# Preamp.net
KiCad netlist of a schematic drawn in EAGLE
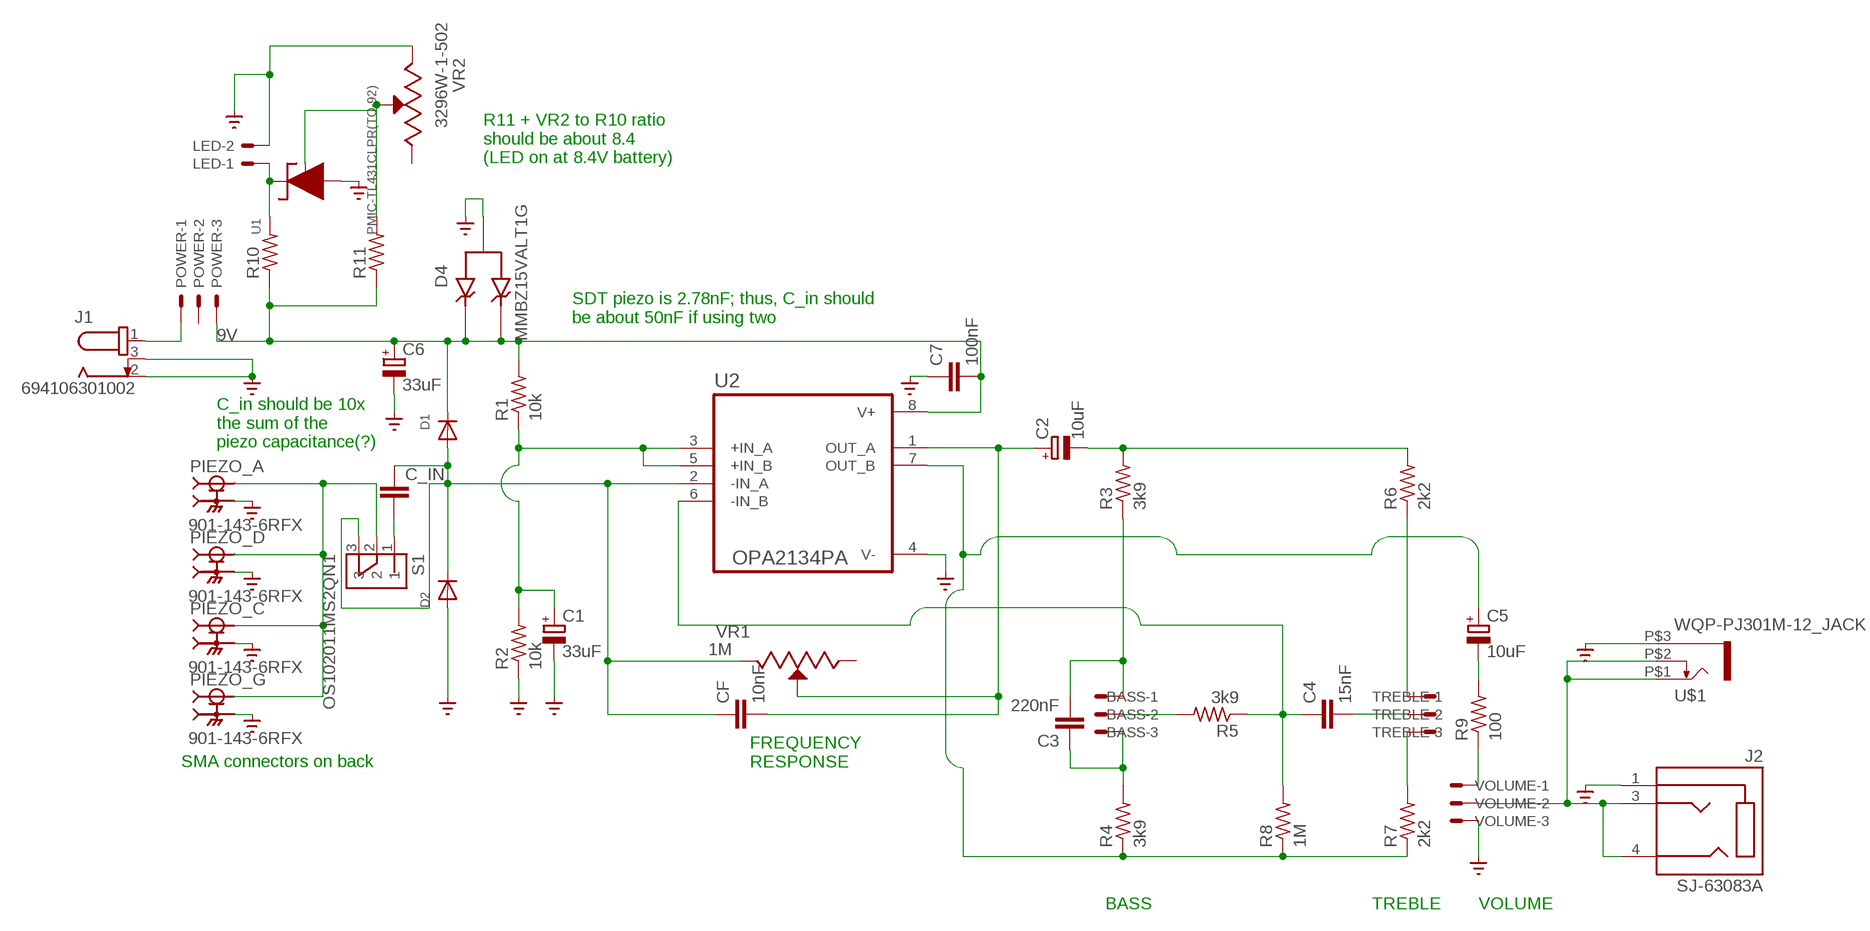
[diagram p0: schematic, sheet 1]

(export (version "E")
  (design (tool "Eeschema 10.0.6"))
  (components
    (comp (ref "BASS")
      (value "JST-XH-03-PIN-LONG-PAD")
      (footprint "eagle-import:JST-XH-03-PACKAGE-LONG-PAD")
      (libsource (lib "eagle-import") (part "JST-XH-03-PIN-LONG-PAD"))
    )
    (comp (ref "C1")
      (value "33uF")
      (footprint "eagle-import:E2,5-6")
      (libsource (lib "eagle-import") (part "CPOL-EUE2.5-6"))
    )
    (comp (ref "C2")
      (value "10uF")
      (footprint "eagle-import:E2,5-6")
      (libsource (lib "eagle-import") (part "CPOL-EUE2.5-6"))
    )
    (comp (ref "C3")
      (value "220nF")
      (footprint "eagle-import:C1206")
      (libsource (lib "eagle-import") (part "C-EUC1206"))
    )
    (comp (ref "C4")
      (value "15nF")
      (footprint "eagle-import:C1206")
      (libsource (lib "eagle-import") (part "C-EUC1206"))
    )
    (comp (ref "C5")
      (value "10uF")
      (footprint "eagle-import:E2,5-6")
      (libsource (lib "eagle-import") (part "CPOL-EUE2.5-6"))
    )
    (comp (ref "C6")
      (value "33uF")
      (footprint "eagle-import:E2,5-6")
      (libsource (lib "eagle-import") (part "CPOL-EUE2.5-6"))
    )
    (comp (ref "C7")
      (value "100nF")
      (footprint "eagle-import:C0603")
      (libsource (lib "eagle-import") (part "C-EUC0603"))
    )
    (comp (ref "CF")
      (value "10nF")
      (footprint "eagle-import:C1206")
      (libsource (lib "eagle-import") (part "C-EUC1206"))
    )
    (comp (ref "C_IN")
      (value "C-EUC0603")
      (footprint "eagle-import:C0603")
      (libsource (lib "eagle-import") (part "C-EUC0603"))
    )
    (comp (ref "D1")
      (value "DIODEDO-1N4148")
      (footprint "eagle-import:DO-1N4148")
      (libsource (lib "eagle-import") (part "DIODEDO-1N4148"))
    )
    (comp (ref "D2")
      (value "DIODEDO-1N4148")
      (footprint "eagle-import:DO-1N4148")
      (libsource (lib "eagle-import") (part "DIODEDO-1N4148"))
    )
    (comp (ref "D4")
      (value "MMBZ15VALT1G")
      (footprint "eagle-import:SOT95P237X111-3N")
      (fields
        (field (name "DIGI-KEY_PART_NUMBER") "MMBZ15VALT1GOSCT-ND")
        (field (name "MF") "ON Semiconductor")
      )
      (libsource (lib "eagle-import") (part "MMBZ15VALT1G"))
    )
    (comp (ref "J1")
      (value "694106301002")
      (footprint "eagle-import:694106301002")
      (fields
        (field (name "DIGIKEY_PART_NUMBER") "732-5930-ND")
        (field (name "MANUFACTURER") "Wurth Electronics Inc.")
        (field (name "CREATED_BY") "PCBLayout.com")
      )
      (libsource (lib "eagle-import") (part "694106301002"))
    )
    (comp (ref "J2")
      (value "SJ-63083A")
      (footprint "eagle-import:CUI_SJ-63083A")
      (fields (field (name "DIGI-KEY_PART_NUMBER") "2223-SJ-63083A-ND") (field (name "MF") "CUI Devices"))
      (libsource (lib "eagle-import") (part "SJ-63083A"))
    )
    (comp (ref "LED")
      (value "JST-XH-02-PIN-ROUND-PAD")
      (footprint "eagle-import:JST-XH-02-PACKAGE-ROUND-PAD")
      (libsource (lib "eagle-import") (part "JST-XH-02-PIN-ROUND-PAD"))
    )
    (comp (ref "PIEZO_A")
      (value "901-143-6RFX")
      (footprint "eagle-import:AMPHENOL_901-143-6RFX")
      (fields (field (name "MF") "Amphenol RF"))
      (libsource (lib "eagle-import") (part "901-143-6RFX"))
    )
    (comp (ref "PIEZO_C")
      (value "901-143-6RFX")
      (footprint "eagle-import:AMPHENOL_901-143-6RFX")
      (fields (field (name "MF") "Amphenol RF"))
      (libsource (lib "eagle-import") (part "901-143-6RFX"))
    )
    (comp (ref "PIEZO_D")
      (value "901-143-6RFX")
      (footprint "eagle-import:AMPHENOL_901-143-6RFX")
      (fields (field (name "MF") "Amphenol RF"))
      (libsource (lib "eagle-import") (part "901-143-6RFX"))
    )
    (comp (ref "PIEZO_G")
      (value "901-143-6RFX")
      (footprint "eagle-import:AMPHENOL_901-143-6RFX")
      (fields (field (name "MF") "Amphenol RF"))
      (libsource (lib "eagle-import") (part "901-143-6RFX"))
    )
    (comp (ref "POWER")
      (value "JST-XH-03-PIN-LONG-PAD")
      (footprint "eagle-import:JST-XH-03-PACKAGE-LONG-PAD")
      (libsource (lib "eagle-import") (part "JST-XH-03-PIN-LONG-PAD"))
    )
    (comp (ref "R1")
      (value "10k")
      (footprint "eagle-import:R1206")
      (libsource (lib "eagle-import") (part "R-US_R1206"))
    )
    (comp (ref "R2")
      (value "10k")
      (footprint "eagle-import:R1206")
      (libsource (lib "eagle-import") (part "R-US_R1206"))
    )
    (comp (ref "R3")
      (value "3k9")
      (footprint "eagle-import:R1206")
      (libsource (lib "eagle-import") (part "R-US_R1206"))
    )
    (comp (ref "R4")
      (value "3k9")
      (footprint "eagle-import:R1206")
      (libsource (lib "eagle-import") (part "R-US_R1206"))
    )
    (comp (ref "R5")
      (value "3k9")
      (footprint "eagle-import:R1206")
      (libsource (lib "eagle-import") (part "R-US_R1206"))
    )
    (comp (ref "R6")
      (value "2k2")
      (footprint "eagle-import:R1206")
      (libsource (lib "eagle-import") (part "R-US_R1206"))
    )
    (comp (ref "R7")
      (value "2k2")
      (footprint "eagle-import:R1206")
      (libsource (lib "eagle-import") (part "R-US_R1206"))
    )
    (comp (ref "R8")
      (value "1M")
      (footprint "eagle-import:R1206")
      (libsource (lib "eagle-import") (part "R-US_R1206"))
    )
    (comp (ref "R9")
      (value "100")
      (footprint "eagle-import:R1206")
      (libsource (lib "eagle-import") (part "R-US_R1206"))
    )
    (comp (ref "R10")
      (value "R-US_R1206")
      (footprint "eagle-import:R1206")
      (libsource (lib "eagle-import") (part "R-US_R1206"))
    )
    (comp (ref "R11")
      (value "R-US_R1206")
      (footprint "eagle-import:R1206")
      (libsource (lib "eagle-import") (part "R-US_R1206"))
    )
    (comp (ref "S1")
      (value "OS102011MS2QN1")
      (footprint "eagle-import:SW_OS102011MS2QN1")
      (fields (field (name "DIGI-KEY_PART_NUMBER") "CKN12284-ND") (field (name "MF") "C&K"))
      (libsource (lib "eagle-import") (part "OS102011MS2QN1"))
    )
    (comp (ref "TREBLE")
      (value "JST-XH-03-PIN-LONG-PAD")
      (footprint "eagle-import:JST-XH-03-PACKAGE-LONG-PAD")
      (libsource (lib "eagle-import") (part "JST-XH-03-PIN-LONG-PAD"))
    )
    (comp (ref "U$1")
      (value "WQP-PJ301M-12_JACK")
      (footprint "eagle-import:WQP-PJ301M-12_JACK")
      (libsource (lib "eagle-import") (part "WQP-PJ301M-12_JACK"))
    )
    (comp (ref "U1")
      (value "PMIC-TL431CLPR(TO-92)")
      (footprint "eagle-import:TO-92")
      (fields (field (name "MF") "Texas Instruments") (field (name "MP") "TL431CLPR"))
      (libsource (lib "eagle-import") (part "PMIC-TL431CLPR(TO-92)"))
    )
    (comp (ref "U2")
      (value "OPA2134PA")
      (footprint "eagle-import:DIP794W45P254L959H508Q8")
      (fields (field (name "MF") "Texas"))
      (libsource (lib "eagle-import") (part "OPA2134PA"))
    )
    (comp (ref "VOLUME")
      (value "JST-XH-03-PIN-LONG-PAD")
      (footprint "eagle-import:JST-XH-03-PACKAGE-LONG-PAD")
      (libsource (lib "eagle-import") (part "JST-XH-03-PIN-LONG-PAD"))
    )
    (comp (ref "VR1")
      (value "1M")
      (footprint "eagle-import:TRIM_3296W-1-502")
      (fields
        (field (name "DIGI-KEY_PART_NUMBER") "3296W-1-502RLFTR-ND")
        (field (name "MF") "Bourns")
        (field (name "MP") "3296W-1-502")
      )
      (libsource (lib "eagle-import") (part "3296W-1-502"))
    )
    (comp (ref "VR2")
      (value "3296W-1-502")
      (footprint "eagle-import:TRIM_3296W-1-502")
      (fields (field (name "DIGI-KEY_PART_NUMBER") "3296W-1-502RLFTR-ND") (field (name "MF") "Bourns"))
      (libsource (lib "eagle-import") (part "3296W-1-502"))
    )
  )
  (nets
    (net (code "1") (name "/9V") (class "Default")
      (node (ref "C6") (pin "+") (pinfunction "+_+") (pintype "passive"))
      (node (ref "C7") (pin "2") (pinfunction "2_2") (pintype "passive"))
      (node (ref "D1") (pin "C") (pinfunction "C_C") (pintype "passive"))
      (node (ref "D4") (pin "1") (pinfunction "K1_1") (pintype "passive"))
      (node (ref "D4") (pin "2") (pinfunction "K2_2") (pintype "passive"))
      (node (ref "POWER") (pin "3") (pinfunction "S_3") (pintype "passive"))
      (node (ref "R1") (pin "2") (pinfunction "2_2") (pintype "passive"))
      (node (ref "R10") (pin "1") (pinfunction "1_1") (pintype "passive"))
      (node (ref "R11") (pin "1") (pinfunction "1_1") (pintype "passive"))
      (node (ref "U2") (pin "8") (pinfunction "V+_8") (pintype "power_in"))
    )
    (net (code "2") (name "Net-(BASSA-S)") (class "Default")
      (node (ref "BASS") (pin "1") (pinfunction "S_1") (pintype "passive"))
      (node (ref "C3") (pin "2") (pinfunction "2_2") (pintype "passive"))
      (node (ref "R3") (pin "1") (pinfunction "1_1") (pintype "passive"))
    )
    (net (code "3") (name "Net-(BASSB-S)") (class "Default")
      (node (ref "BASS") (pin "2") (pinfunction "S_2") (pintype "passive"))
      (node (ref "R5") (pin "2") (pinfunction "2_2") (pintype "passive"))
    )
    (net (code "4") (name "Net-(BASSC-S)") (class "Default")
      (node (ref "BASS") (pin "3") (pinfunction "S_3") (pintype "passive"))
      (node (ref "C3") (pin "1") (pinfunction "1_1") (pintype "passive"))
      (node (ref "R4") (pin "2") (pinfunction "2_2") (pintype "passive"))
    )
    (net (code "5") (name "Net-(C2-Pad-)") (class "Default")
      (node (ref "C2") (pin "-") (pinfunction "-_-") (pintype "passive"))
      (node (ref "R3") (pin "2") (pinfunction "2_2") (pintype "passive"))
      (node (ref "R6") (pin "2") (pinfunction "2_2") (pintype "passive"))
    )
    (net (code "6") (name "Net-(C5-Pad-)") (class "Default")
      (node (ref "C5") (pin "-") (pinfunction "-_-") (pintype "passive"))
      (node (ref "R9") (pin "2") (pinfunction "2_2") (pintype "passive"))
    )
    (net (code "7") (name "Net-(C_IN-Pad2)") (class "Default")
      (node (ref "C_IN") (pin "2") (pinfunction "2_2") (pintype "passive"))
      (node (ref "S1") (pin "1") (pinfunction "1_1") (pintype "passive"))
    )
    (net (code "8") (name "Net-(J2-RING)") (class "Default")
      (node (ref "J2") (pin "3") (pinfunction "TIP_3") (pintype "passive"))
      (node (ref "J2") (pin "4") (pinfunction "RING_4") (pintype "passive"))
      (node (ref "U$1") (pin "P$1") (pinfunction "2_P$1") (pintype "passive"))
      (node (ref "U$1") (pin "P$2") (pinfunction "3_P$2") (pintype "passive"))
      (node (ref "VOLUME") (pin "2") (pinfunction "S_2") (pintype "passive"))
    )
    (net (code "9") (name "Net-(LEDA-S)") (class "Default")
      (node (ref "LED") (pin "1") (pinfunction "S_1") (pintype "passive"))
      (node (ref "R10") (pin "2") (pinfunction "2_2") (pintype "passive"))
      (node (ref "U1") (pin "1") (pinfunction "CATHODE_1") (pintype "bidirectional"))
    )
    (net (code "10") (name "Net-(PIEZO_A-Pad1)") (class "Default")
      (node (ref "PIEZO_A") (pin "1") (pinfunction "1_1") (pintype "passive"))
      (node (ref "PIEZO_C") (pin "1") (pinfunction "1_1") (pintype "passive"))
      (node (ref "PIEZO_D") (pin "1") (pinfunction "1_1") (pintype "passive"))
      (node (ref "PIEZO_G") (pin "1") (pinfunction "1_1") (pintype "passive"))
      (node (ref "S1") (pin "2") (pinfunction "2_2") (pintype "passive"))
    )
    (net (code "11") (name "Net-(POWERA-S)") (class "Default")
      (node (ref "J1") (pin "1") (pinfunction "1_1") (pintype "passive"))
      (node (ref "POWER") (pin "1") (pinfunction "S_1") (pintype "passive"))
    )
    (net (code "12") (name "Net-(TREBLEA-S)") (class "Default")
      (node (ref "R6") (pin "1") (pinfunction "1_1") (pintype "passive"))
      (node (ref "TREBLE") (pin "1") (pinfunction "S_1") (pintype "passive"))
    )
    (net (code "13") (name "Net-(TREBLEB-S)") (class "Default")
      (node (ref "C4") (pin "2") (pinfunction "2_2") (pintype "passive"))
      (node (ref "TREBLE") (pin "2") (pinfunction "S_2") (pintype "passive"))
    )
    (net (code "14") (name "Net-(TREBLEC-S)") (class "Default")
      (node (ref "R7") (pin "2") (pinfunction "2_2") (pintype "passive"))
      (node (ref "TREBLE") (pin "3") (pinfunction "S_3") (pintype "passive"))
    )
    (net (code "15") (name "Net-(U1-REF)") (class "Default")
      (node (ref "R11") (pin "2") (pinfunction "2_2") (pintype "passive"))
      (node (ref "U1") (pin "3") (pinfunction "REF_3") (pintype "bidirectional"))
      (node (ref "VR2") (pin "2") (pinfunction "WIPER_2") (pintype "passive"))
    )
    (net (code "16") (name "Net-(U2-+IN_A)") (class "Default")
      (node (ref "C1") (pin "+") (pinfunction "+_+") (pintype "passive"))
      (node (ref "R1") (pin "1") (pinfunction "1_1") (pintype "passive"))
      (node (ref "R2") (pin "2") (pinfunction "2_2") (pintype "passive"))
      (node (ref "U2") (pin "3") (pinfunction "+IN_A_3") (pintype "input"))
      (node (ref "U2") (pin "5") (pinfunction "+IN_B_5") (pintype "input"))
    )
    (net (code "17") (name "Net-(U2--IN_A)") (class "Default")
      (node (ref "CF") (pin "1") (pinfunction "1_1") (pintype "passive"))
      (node (ref "C_IN") (pin "1") (pinfunction "1_1") (pintype "passive"))
      (node (ref "D1") (pin "A") (pinfunction "A_A") (pintype "passive"))
      (node (ref "D2") (pin "C") (pinfunction "C_C") (pintype "passive"))
      (node (ref "S1") (pin "3") (pinfunction "3_3") (pintype "passive"))
      (node (ref "U2") (pin "2") (pinfunction "-IN_A_2") (pintype "input"))
      (node (ref "VR1") (pin "3") (pinfunction "CW_3") (pintype "passive"))
    )
    (net (code "18") (name "Net-(U2--IN_B)") (class "Default")
      (node (ref "C4") (pin "1") (pinfunction "1_1") (pintype "passive"))
      (node (ref "R5") (pin "1") (pinfunction "1_1") (pintype "passive"))
      (node (ref "R8") (pin "2") (pinfunction "2_2") (pintype "passive"))
      (node (ref "U2") (pin "6") (pinfunction "-IN_B_6") (pintype "input"))
    )
    (net (code "19") (name "Net-(U2-OUT_A)") (class "Default")
      (node (ref "C2") (pin "+") (pinfunction "+_+") (pintype "passive"))
      (node (ref "CF") (pin "2") (pinfunction "2_2") (pintype "passive"))
      (node (ref "U2") (pin "1") (pinfunction "OUT_A_1") (pintype "output"))
      (node (ref "VR1") (pin "2") (pinfunction "WIPER_2") (pintype "passive"))
    )
    (net (code "20") (name "Net-(U2-OUT_B)") (class "Default")
      (node (ref "C5") (pin "+") (pinfunction "+_+") (pintype "passive"))
      (node (ref "R4") (pin "1") (pinfunction "1_1") (pintype "passive"))
      (node (ref "R7") (pin "1") (pinfunction "1_1") (pintype "passive"))
      (node (ref "R8") (pin "1") (pinfunction "1_1") (pintype "passive"))
      (node (ref "U2") (pin "7") (pinfunction "OUT_B_7") (pintype "output"))
    )
    (net (code "21") (name "Net-(VOLUMEA-S)") (class "Default")
      (node (ref "R9") (pin "1") (pinfunction "1_1") (pintype "passive"))
      (node (ref "VOLUME") (pin "1") (pinfunction "S_1") (pintype "passive"))
    )
    (net (code "22") (name "SUPPLY0_GND_") (class "Default")
      (node (ref "C1") (pin "-") (pinfunction "-_-") (pintype "passive"))
      (node (ref "C6") (pin "-") (pinfunction "-_-") (pintype "passive"))
      (node (ref "C7") (pin "1") (pinfunction "1_1") (pintype "passive"))
      (node (ref "D2") (pin "A") (pinfunction "A_A") (pintype "passive"))
      (node (ref "D4") (pin "3") (pinfunction "A_3") (pintype "passive"))
      (node (ref "J1") (pin "2") (pinfunction "2_2") (pintype "passive"))
      (node (ref "J1") (pin "3") (pinfunction "3_3") (pintype "passive"))
      (node (ref "J2") (pin "1") (pinfunction "SLEEVE_1") (pintype "passive"))
      (node (ref "LED") (pin "2") (pinfunction "S_2") (pintype "passive"))
      (node (ref "PIEZO_A") (pin "S1") (pinfunction "2_S1") (pintype "passive"))
      (node (ref "PIEZO_A") (pin "S2") (pinfunction "2_S2") (pintype "passive"))
      (node (ref "PIEZO_A") (pin "S3") (pinfunction "2_S3") (pintype "passive"))
      (node (ref "PIEZO_A") (pin "S4") (pinfunction "2_S4") (pintype "passive"))
      (node (ref "PIEZO_C") (pin "S1") (pinfunction "2_S1") (pintype "passive"))
      (node (ref "PIEZO_C") (pin "S2") (pinfunction "2_S2") (pintype "passive"))
      (node (ref "PIEZO_C") (pin "S3") (pinfunction "2_S3") (pintype "passive"))
      (node (ref "PIEZO_C") (pin "S4") (pinfunction "2_S4") (pintype "passive"))
      (node (ref "PIEZO_D") (pin "S1") (pinfunction "2_S1") (pintype "passive"))
      (node (ref "PIEZO_D") (pin "S2") (pinfunction "2_S2") (pintype "passive"))
      (node (ref "PIEZO_D") (pin "S3") (pinfunction "2_S3") (pintype "passive"))
      (node (ref "PIEZO_D") (pin "S4") (pinfunction "2_S4") (pintype "passive"))
      (node (ref "PIEZO_G") (pin "S1") (pinfunction "2_S1") (pintype "passive"))
      (node (ref "PIEZO_G") (pin "S2") (pinfunction "2_S2") (pintype "passive"))
      (node (ref "PIEZO_G") (pin "S3") (pinfunction "2_S3") (pintype "passive"))
      (node (ref "PIEZO_G") (pin "S4") (pinfunction "2_S4") (pintype "passive"))
      (node (ref "R2") (pin "1") (pinfunction "1_1") (pintype "passive"))
      (node (ref "U$1") (pin "P$3") (pinfunction "1_P$3") (pintype "passive"))
      (node (ref "U1") (pin "2") (pinfunction "ANODE_2") (pintype "bidirectional"))
      (node (ref "U2") (pin "4") (pinfunction "V-_4") (pintype "power_in"))
      (node (ref "VOLUME") (pin "3") (pinfunction "S_3") (pintype "passive"))
      (node (ref "VR2") (pin "3") (pinfunction "CW_3") (pintype "passive"))
    )
    (net (code "23") (name "unconnected-(POWERB-S-Pad2)") (class "Default")
      (node (ref "POWER") (pin "2") (pinfunction "S_2") (pintype "passive"))
    )
    (net (code "24") (name "unconnected-(VR1-CCW-Pad1)") (class "Default")
      (node (ref "VR1") (pin "1") (pinfunction "CCW_1") (pintype "passive"))
    )
    (net (code "25") (name "unconnected-(VR2-CCW-Pad1)") (class "Default")
      (node (ref "VR2") (pin "1") (pinfunction "CCW_1") (pintype "passive"))
    )
  )
)
